# mcu.net
KiCad netlist of a schematic drawn in Altium Designer
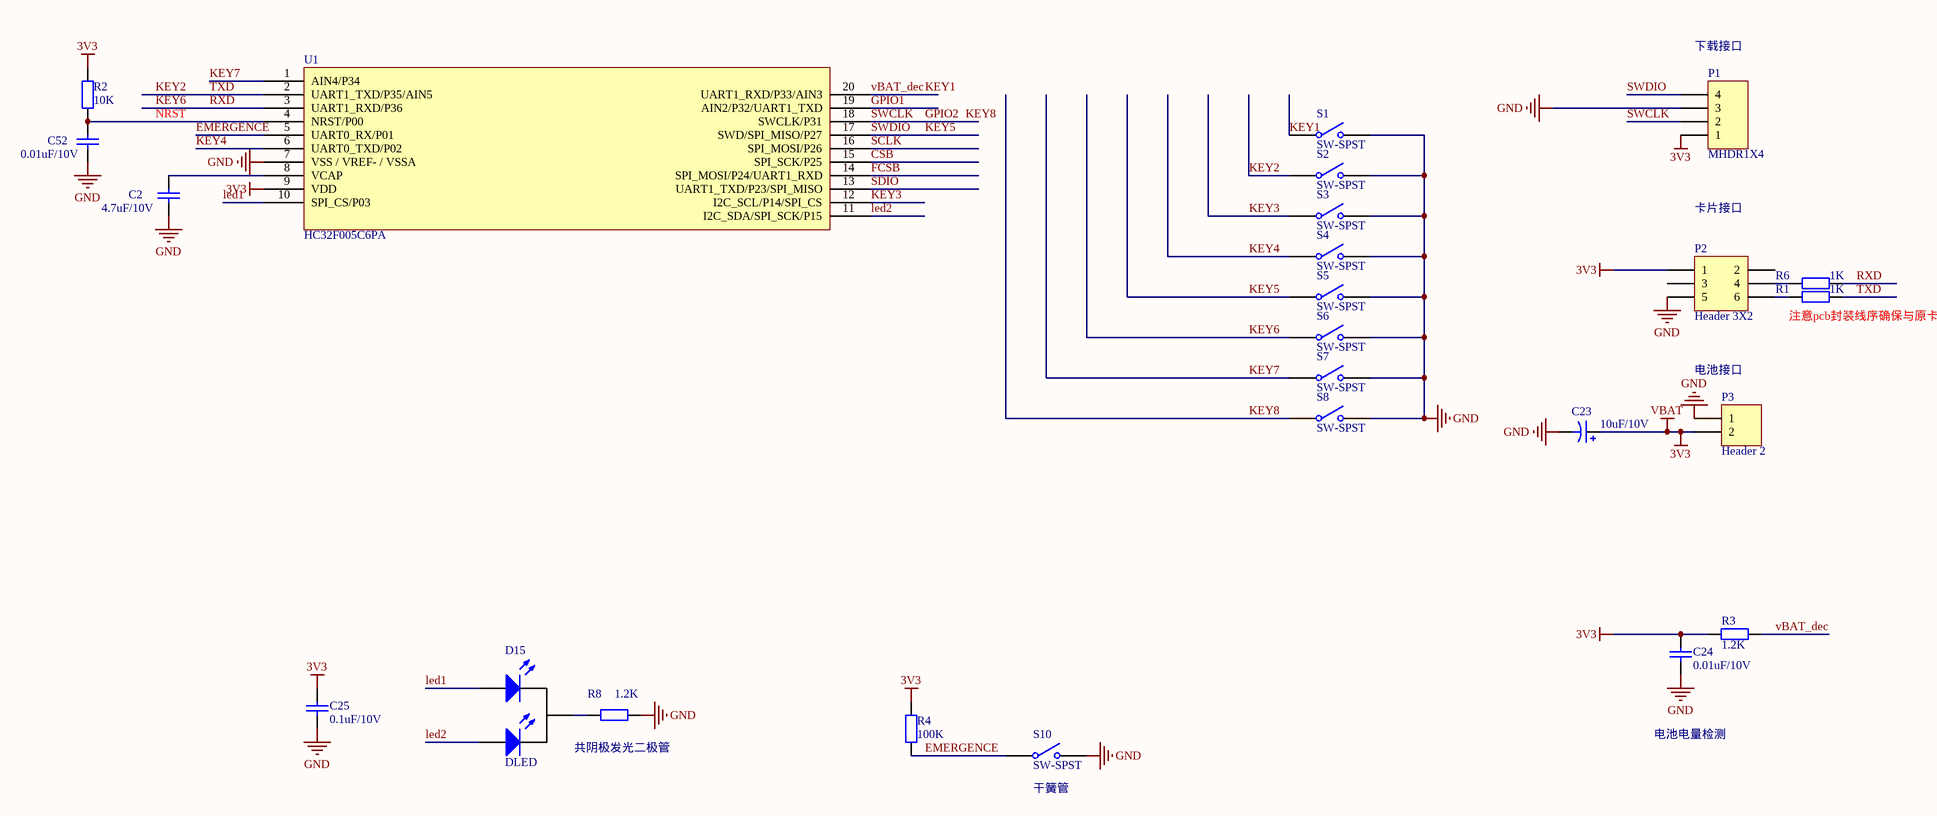
[diagram p0: mcu.SchDoc]

(export (version "E")
  (design (tool "Eeschema 10.0.6"))
  (components
    (comp (ref "C2")
      (value "4.7uF/10V")
      (footprint "0603C")
      (description "Capacitor")
      (fields (field (name "PUBLISHER") "Altium Limited"))
      (libsource (lib "Miscellaneous Devices") (part "Cap"))
    )
    (comp (ref "C23")
      (value "10uF/10V")
      (description "Polarized Capacitor (Radial)")
      (fields (field (name "PUBLISHER") "Altium Limited"))
      (libsource (lib "Miscellaneous Devices") (part "Cap Pol1"))
    )
    (comp (ref "C24")
      (value "0.01uF/10V")
      (footprint "0603C")
      (description "Capacitor")
      (fields (field (name "PUBLISHER") "Altium Limited"))
      (libsource (lib "Miscellaneous Devices") (part "Cap"))
    )
    (comp (ref "C25")
      (value "0.1uF/10V")
      (footprint "0603C")
      (description "Capacitor")
      (fields (field (name "PUBLISHER") "Altium Limited"))
      (libsource (lib "Miscellaneous Devices") (part "Cap"))
    )
    (comp (ref "C52")
      (value "0.01uF/10V")
      (footprint "0603C")
      (description "Capacitor")
      (fields (field (name "PUBLISHER") "Altium Limited"))
      (libsource (lib "Miscellaneous Devices") (part "Cap"))
    )
    (comp (ref "D15") (value "DLED") (libsource (lib "Schlib_20110825") (part "DLED")))
    (comp (ref "P1")
      (value "MHDR1X4")
      (footprint "SIP4")
      (description "Header, 4-Pin")
      (fields (field (name "PUBLISHER") "Altium Limited"))
      (libsource (lib "Miscellaneous Connectors") (part "MHDR1X4"))
    )
    (comp (ref "P2")
      (value "Header 3X2")
      (description "Header, 3-Pin, Dual row")
      (fields (field (name "PUBLISHER") "Altium Limited"))
      (libsource (lib "Miscellaneous Connectors") (part "Header 3X2"))
    )
    (comp (ref "P3")
      (value "Header 2")
      (description "Header, 2-Pin")
      (fields (field (name "PUBLISHER") "Altium Limited"))
      (libsource (lib "Miscellaneous Connectors") (part "Header 2"))
    )
    (comp (ref "R1")
      (value "1K")
      (footprint "0603R")
      (description "Resistor")
      (fields (field (name "PUBLISHER") "Altium Limited"))
      (libsource (lib "Miscellaneous Devices") (part "Res2"))
    )
    (comp (ref "R2")
      (value "10K")
      (footprint "0603R")
      (description "Resistor")
      (fields (field (name "PUBLISHER") "Altium Limited"))
      (libsource (lib "") (part "Res2_1"))
    )
    (comp (ref "R3")
      (value "1.2K")
      (footprint "0603R")
      (description "Resistor")
      (fields (field (name "PUBLISHER") "Altium Limited"))
      (libsource (lib "Miscellaneous Devices") (part "Res2"))
    )
    (comp (ref "R4")
      (value "100K")
      (footprint "0603R")
      (description "Resistor")
      (fields (field (name "PUBLISHER") "Altium Limited"))
      (libsource (lib "") (part "Res2_2"))
    )
    (comp (ref "R6")
      (value "1K")
      (footprint "0603R")
      (description "Resistor")
      (fields (field (name "PUBLISHER") "Altium Limited"))
      (libsource (lib "Miscellaneous Devices") (part "Res2"))
    )
    (comp (ref "R8")
      (value "1.2K")
      (footprint "0603R")
      (description "Resistor")
      (fields (field (name "PUBLISHER") "Altium Limited"))
      (libsource (lib "Miscellaneous Devices") (part "Res2"))
    )
    (comp (ref "S1")
      (value "SW-SPST")
      (description "Single-Pole, Single-Throw Switch")
      (fields (field (name "PUBLISHER") "Altium Limited"))
      (libsource (lib "Miscellaneous Devices") (part "SW-SPST"))
    )
    (comp (ref "S2")
      (value "SW-SPST")
      (description "Single-Pole, Single-Throw Switch")
      (fields (field (name "PUBLISHER") "Altium Limited"))
      (libsource (lib "Miscellaneous Devices") (part "SW-SPST"))
    )
    (comp (ref "S3")
      (value "SW-SPST")
      (description "Single-Pole, Single-Throw Switch")
      (fields (field (name "PUBLISHER") "Altium Limited"))
      (libsource (lib "Miscellaneous Devices") (part "SW-SPST"))
    )
    (comp (ref "S4")
      (value "SW-SPST")
      (description "Single-Pole, Single-Throw Switch")
      (fields (field (name "PUBLISHER") "Altium Limited"))
      (libsource (lib "Miscellaneous Devices") (part "SW-SPST"))
    )
    (comp (ref "S5")
      (value "SW-SPST")
      (description "Single-Pole, Single-Throw Switch")
      (fields (field (name "PUBLISHER") "Altium Limited"))
      (libsource (lib "Miscellaneous Devices") (part "SW-SPST"))
    )
    (comp (ref "S6")
      (value "SW-SPST")
      (description "Single-Pole, Single-Throw Switch")
      (fields (field (name "PUBLISHER") "Altium Limited"))
      (libsource (lib "Miscellaneous Devices") (part "SW-SPST"))
    )
    (comp (ref "S7")
      (value "SW-SPST")
      (description "Single-Pole, Single-Throw Switch")
      (fields (field (name "PUBLISHER") "Altium Limited"))
      (libsource (lib "Miscellaneous Devices") (part "SW-SPST"))
    )
    (comp (ref "S8")
      (value "SW-SPST")
      (description "Single-Pole, Single-Throw Switch")
      (fields (field (name "PUBLISHER") "Altium Limited"))
      (libsource (lib "Miscellaneous Devices") (part "SW-SPST"))
    )
    (comp (ref "S10")
      (value "SW-SPST")
      (description "Single-Pole, Single-Throw Switch")
      (fields (field (name "PUBLISHER") "Altium Limited"))
      (libsource (lib "Miscellaneous Devices") (part "SW-SPST"))
    )
    (comp (ref "U1") (value "HC32F005C6PA") (libsource (lib "Schlib_20110825") (part "HC32F005C6PA")))
  )
  (nets
    (net (code "1") (name "/CSB") (class "Default")
      (node (ref "U1") (pin "15") (pinfunction "SPI_SCK/P25_15") (pintype "passive"))
    )
    (net (code "2") (name "/EMERGENCE") (class "Default")
      (node (ref "R4") (pin "2") (pinfunction "2_2") (pintype "passive"))
      (node (ref "S10") (pin "1") (pinfunction "COMMON_1") (pintype "passive"))
      (node (ref "U1") (pin "5") (pinfunction "UART0_RX/P01_5") (pintype "passive"))
    )
    (net (code "3") (name "/FCSB") (class "Default")
      (node (ref "U1") (pin "14") (pinfunction "SPI_MOSI/P24/UART1_RXD_14") (pintype "passive"))
    )
    (net (code "4") (name "/GPIO1") (class "Default")
      (node (ref "U1") (pin "19") (pinfunction "AIN2/P32/UART1_TXD_19") (pintype "passive"))
    )
    (net (code "5") (name "/GPIO2") (class "Default")
      (node (ref "P1") (pin "2") (pinfunction "2_2") (pintype "passive"))
      (node (ref "S8") (pin "1") (pinfunction "COMMON_1") (pintype "passive"))
      (node (ref "U1") (pin "18") (pinfunction "SWCLK/P31_18") (pintype "passive"))
    )
    (net (code "6") (name "/KEY1") (class "Default")
      (node (ref "R3") (pin "1") (pinfunction "1_1") (pintype "passive"))
      (node (ref "S1") (pin "1") (pinfunction "COMMON_1") (pintype "passive"))
      (node (ref "U1") (pin "20") (pinfunction "UART1_RXD/P33/AIN3_20") (pintype "passive"))
    )
    (net (code "7") (name "/KEY2") (class "Default")
      (node (ref "R1") (pin "1") (pinfunction "1_1") (pintype "passive"))
      (node (ref "S2") (pin "1") (pinfunction "COMMON_1") (pintype "passive"))
      (node (ref "U1") (pin "2") (pinfunction "UART1_TXD/P35/AIN5_2") (pintype "passive"))
    )
    (net (code "8") (name "/KEY3") (class "Default")
      (node (ref "S3") (pin "1") (pinfunction "COMMON_1") (pintype "passive"))
      (node (ref "U1") (pin "12") (pinfunction "I2C_SCL/P14/SPI_CS_12") (pintype "passive"))
    )
    (net (code "9") (name "/KEY4") (class "Default")
      (node (ref "S4") (pin "1") (pinfunction "COMMON_1") (pintype "passive"))
      (node (ref "U1") (pin "6") (pinfunction "UART0_TXD/P02_6") (pintype "passive"))
    )
    (net (code "10") (name "/KEY5") (class "Default")
      (node (ref "P1") (pin "4") (pinfunction "4_4") (pintype "passive"))
      (node (ref "S5") (pin "1") (pinfunction "COMMON_1") (pintype "passive"))
      (node (ref "U1") (pin "17") (pinfunction "SWD/SPI_MISO/P27_17") (pintype "passive"))
    )
    (net (code "11") (name "/KEY6") (class "Default")
      (node (ref "R6") (pin "1") (pinfunction "1_1") (pintype "passive"))
      (node (ref "S6") (pin "1") (pinfunction "COMMON_1") (pintype "passive"))
      (node (ref "U1") (pin "3") (pinfunction "UART1_RXD/P36_3") (pintype "passive"))
    )
    (net (code "12") (name "/KEY7") (class "Default")
      (node (ref "S7") (pin "1") (pinfunction "COMMON_1") (pintype "passive"))
      (node (ref "U1") (pin "1") (pinfunction "AIN4/P34_1") (pintype "passive"))
    )
    (net (code "13") (name "/NRST") (class "Default")
      (node (ref "C52") (pin "1") (pinfunction "1_1") (pintype "passive"))
      (node (ref "R2") (pin "1") (pinfunction "1_1") (pintype "passive"))
      (node (ref "U1") (pin "4") (pinfunction "NRST/P00_4") (pintype "passive"))
    )
    (net (code "14") (name "/SCLK") (class "Default")
      (node (ref "U1") (pin "16") (pinfunction "SPI_MOSI/P26_16") (pintype "passive"))
    )
    (net (code "15") (name "/SDIO") (class "Default")
      (node (ref "U1") (pin "13") (pinfunction "UART1_TXD/P23/SPI_MISO_13") (pintype "passive"))
    )
    (net (code "16") (name "/led1") (class "Default")
      (node (ref "D15") (pin "1") (pinfunction "A_1") (pintype "passive"))
      (node (ref "U1") (pin "10") (pinfunction "SPI_CS/P03_10") (pintype "passive"))
    )
    (net (code "17") (name "/led2") (class "Default")
      (node (ref "D15") (pin "3") (pinfunction "A_3") (pintype "passive"))
      (node (ref "U1") (pin "11") (pinfunction "I2C_SDA/SPI_SCK/P15_11") (pintype "passive"))
    )
    (net (code "18") (name "3V3") (class "Default")
      (node (ref "C23") (pin "1") (pinfunction "1_1") (pintype "passive"))
      (node (ref "C24") (pin "1") (pinfunction "1_1") (pintype "passive"))
      (node (ref "C25") (pin "1") (pinfunction "1_1") (pintype "passive"))
      (node (ref "P1") (pin "1") (pinfunction "1_1") (pintype "passive"))
      (node (ref "P2") (pin "1") (pinfunction "1_1") (pintype "passive"))
      (node (ref "P3") (pin "2") (pinfunction "2_2") (pintype "passive"))
      (node (ref "R2") (pin "2") (pinfunction "2_2") (pintype "passive"))
      (node (ref "R3") (pin "2") (pinfunction "2_2") (pintype "passive"))
      (node (ref "R4") (pin "1") (pinfunction "1_1") (pintype "passive"))
      (node (ref "U1") (pin "9") (pinfunction "VDD_9") (pintype "passive"))
    )
    (net (code "19") (name "GND") (class "Default")
      (node (ref "C2") (pin "2") (pinfunction "2_2") (pintype "passive"))
      (node (ref "C23") (pin "2") (pinfunction "2_2") (pintype "passive"))
      (node (ref "C24") (pin "2") (pinfunction "2_2") (pintype "passive"))
      (node (ref "C25") (pin "2") (pinfunction "2_2") (pintype "passive"))
      (node (ref "C52") (pin "2") (pinfunction "2_2") (pintype "passive"))
      (node (ref "P1") (pin "3") (pinfunction "3_3") (pintype "passive"))
      (node (ref "P2") (pin "5") (pinfunction "5_5") (pintype "passive"))
      (node (ref "P3") (pin "1") (pinfunction "1_1") (pintype "passive"))
      (node (ref "R8") (pin "1") (pinfunction "1_1") (pintype "passive"))
      (node (ref "S1") (pin "2") (pinfunction "NO_2") (pintype "passive"))
      (node (ref "S10") (pin "2") (pinfunction "NO_2") (pintype "passive"))
      (node (ref "S2") (pin "2") (pinfunction "NO_2") (pintype "passive"))
      (node (ref "S3") (pin "2") (pinfunction "NO_2") (pintype "passive"))
      (node (ref "S4") (pin "2") (pinfunction "NO_2") (pintype "passive"))
      (node (ref "S5") (pin "2") (pinfunction "NO_2") (pintype "passive"))
      (node (ref "S6") (pin "2") (pinfunction "NO_2") (pintype "passive"))
      (node (ref "S7") (pin "2") (pinfunction "NO_2") (pintype "passive"))
      (node (ref "S8") (pin "2") (pinfunction "NO_2") (pintype "passive"))
      (node (ref "U1") (pin "7") (pinfunction "VSS_/_VREF-_/_VSSA_7") (pintype "passive"))
    )
    (net (code "20") (name "Net-(D15-K)") (class "Default")
      (node (ref "D15") (pin "2") (pinfunction "K_2") (pintype "passive"))
      (node (ref "R8") (pin "2") (pinfunction "2_2") (pintype "passive"))
    )
    (net (code "21") (name "Net-(P2-Pad4)") (class "Default")
      (node (ref "P2") (pin "4") (pinfunction "4_4") (pintype "passive"))
      (node (ref "R6") (pin "2") (pinfunction "2_2") (pintype "passive"))
    )
    (net (code "22") (name "Net-(P2-Pad6)") (class "Default")
      (node (ref "P2") (pin "6") (pinfunction "6_6") (pintype "passive"))
      (node (ref "R1") (pin "2") (pinfunction "2_2") (pintype "passive"))
    )
    (net (code "23") (name "Net-(U1-VCAP)") (class "Default")
      (node (ref "C2") (pin "1") (pinfunction "1_1") (pintype "passive"))
      (node (ref "U1") (pin "8") (pinfunction "VCAP_8") (pintype "passive"))
    )
    (net (code "24") (name "unconnected-(P2-Pad2)") (class "Default")
      (node (ref "P2") (pin "2") (pinfunction "2_2") (pintype "passive"))
    )
    (net (code "25") (name "unconnected-(P2-Pad3)") (class "Default")
      (node (ref "P2") (pin "3") (pinfunction "3_3") (pintype "passive"))
    )
  )
)
